# MEMS_audio_board.net
KiCad netlist of a schematic drawn in EAGLE
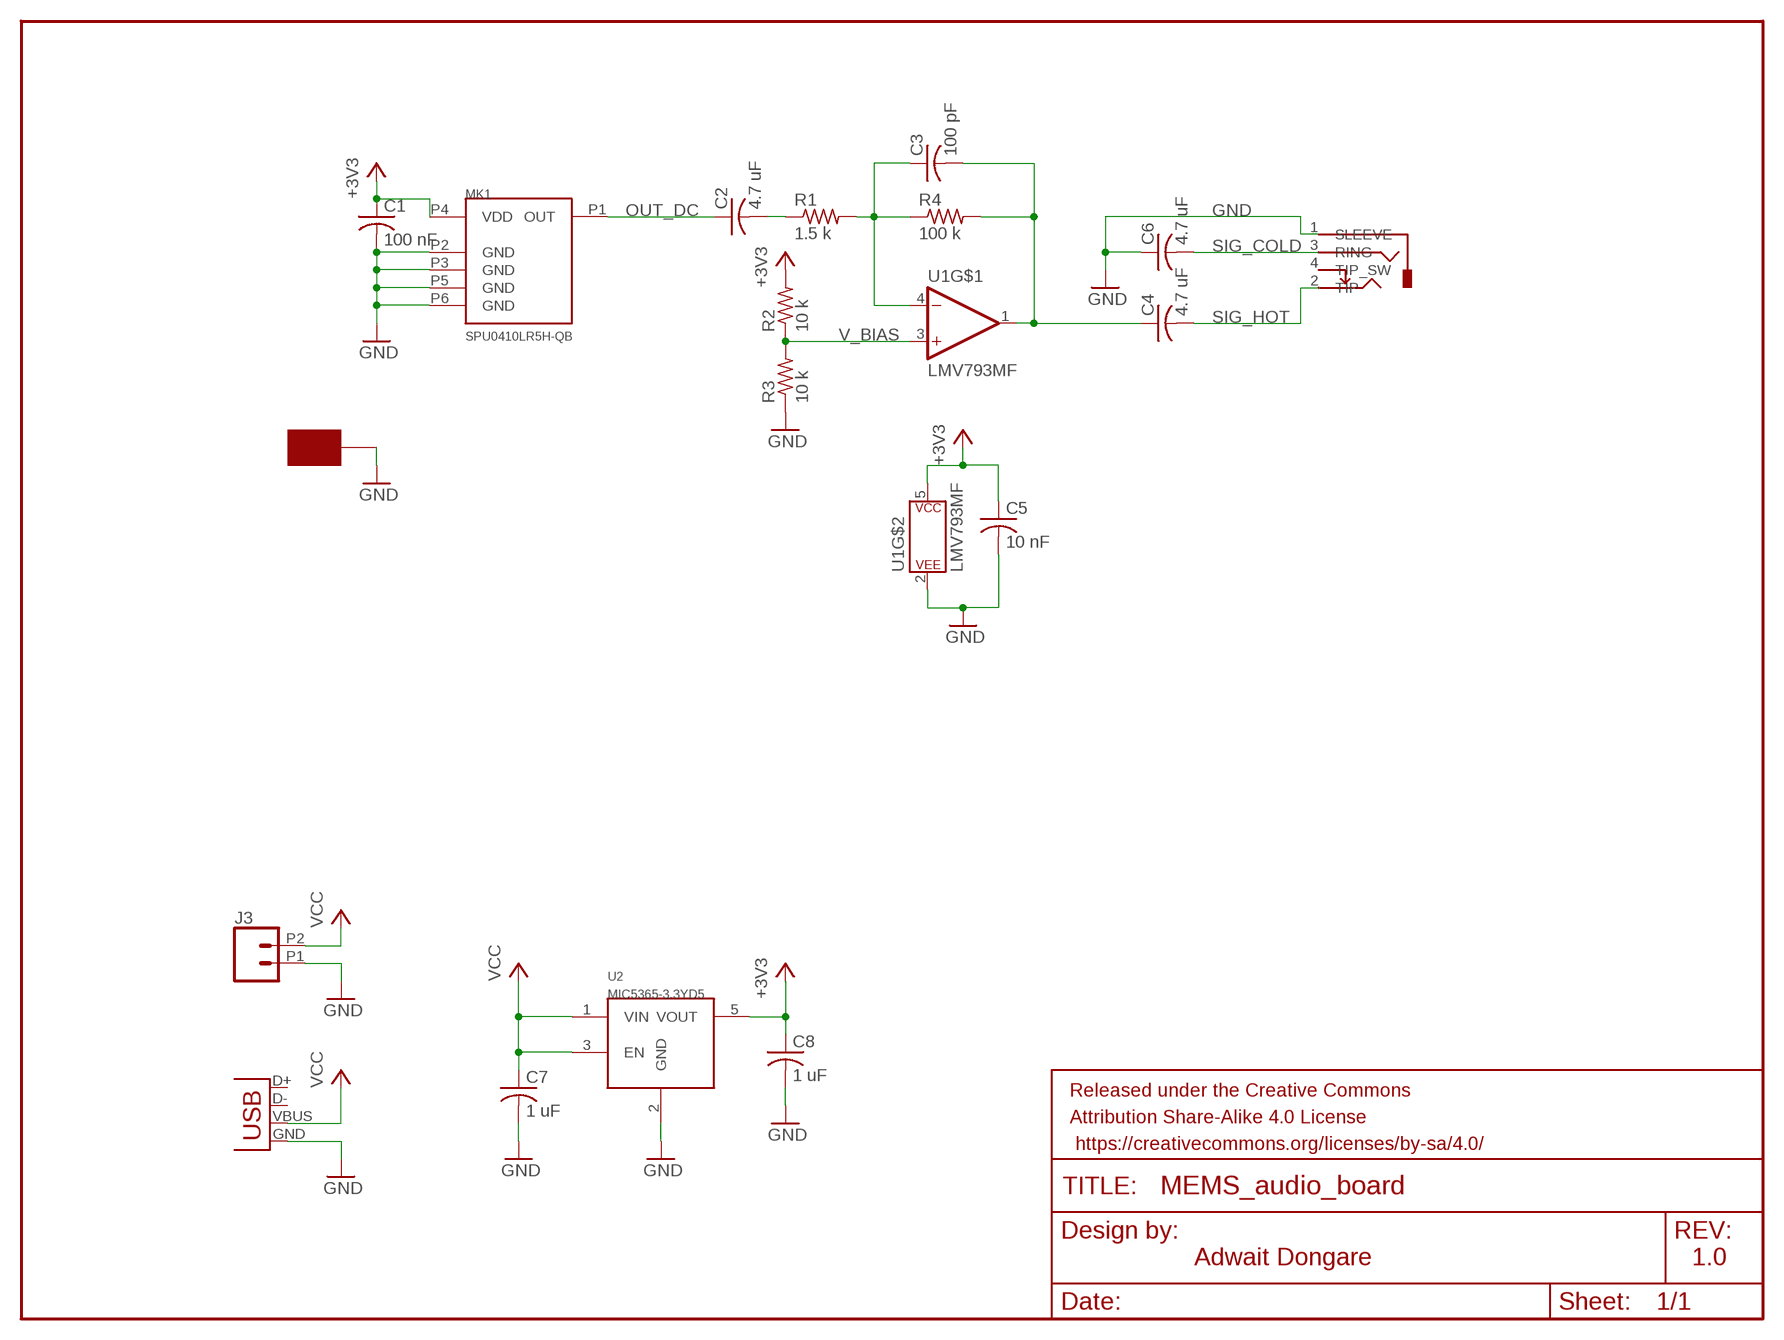
[diagram p0: schematic, sheet 1]

(export (version "E")
  (design (tool "Eeschema 10.0.6"))
  (components
    (comp (ref "C1")
      (value "100 nF")
      (footprint "eagle-import:C0603")
      (libsource (lib "eagle-import") (part "C-USC0603"))
    )
    (comp (ref "C2")
      (value "4.7 uF")
      (footprint "eagle-import:C0603")
      (libsource (lib "eagle-import") (part "C-USC0603"))
    )
    (comp (ref "C3")
      (value "100 pF")
      (footprint "eagle-import:C0603")
      (libsource (lib "eagle-import") (part "C-USC0603"))
    )
    (comp (ref "C4")
      (value "4.7 uF")
      (footprint "eagle-import:C0603")
      (libsource (lib "eagle-import") (part "C-USC0603"))
    )
    (comp (ref "C5")
      (value "10 nF")
      (footprint "eagle-import:C0603")
      (libsource (lib "eagle-import") (part "C-USC0603"))
    )
    (comp (ref "C6")
      (value "4.7 uF")
      (footprint "eagle-import:C0603")
      (libsource (lib "eagle-import") (part "C-USC0603"))
    )
    (comp (ref "C7")
      (value "1 uF")
      (footprint "eagle-import:C0603")
      (libsource (lib "eagle-import") (part "C-USC0603"))
    )
    (comp (ref "C8")
      (value "1 uF")
      (footprint "eagle-import:C0603")
      (libsource (lib "eagle-import") (part "C-USC0603"))
    )
    (comp (ref "FRAME1")
      (value "FRAME-LETTERNO_PACKAGE")
      (footprint "eagle-import:DUMMY")
      (fields (field (name "DESIGNER") "Nobody"))
      (libsource (lib "eagle-import") (part "FRAME-LETTERNO_PACKAGE"))
    )
    (comp (ref "J1")
      (value "SJ-2524-SMT")
      (footprint "eagle-import:SJ-2524-SMT")
      (libsource (lib "eagle-import") (part "SJ-2524-SMT"))
    )
    (comp (ref "J2")
      (value "USBSMD")
      (footprint "eagle-import:USB-MINIB")
      (libsource (lib "eagle-import") (part "USBSMD"))
    )
    (comp (ref "J3")
      (value "CONN_022.54MM_SCREWTERM")
      (footprint "eagle-import:1X02_2.54_SCREWTERM")
      (libsource (lib "eagle-import") (part "CONN_022.54MM_SCREWTERM"))
    )
    (comp (ref "MK1")
      (value "SPU0410LR5H-QB")
      (footprint "eagle-import:SPU0410LR5H-QB")
      (libsource (lib "eagle-import") (part "SPU0410LR5H-QB"))
    )
    (comp (ref "R1")
      (value "1.5 k")
      (footprint "eagle-import:R0603")
      (libsource (lib "eagle-import") (part "R-US_R0603"))
    )
    (comp (ref "R2")
      (value "10 k")
      (footprint "eagle-import:R0603")
      (libsource (lib "eagle-import") (part "R-US_R0603"))
    )
    (comp (ref "R3")
      (value "10 k")
      (footprint "eagle-import:R0603")
      (libsource (lib "eagle-import") (part "R-US_R0603"))
    )
    (comp (ref "R4")
      (value "100 k")
      (footprint "eagle-import:R0603")
      (libsource (lib "eagle-import") (part "R-US_R0603"))
    )
    (comp (ref "TP")
      (value "TEST_PAD-0.4X0.1")
      (footprint "eagle-import:TESTPAD_10.16X2.54")
      (libsource (lib "eagle-import") (part "TEST_PAD-0.4X0.1"))
    )
    (comp (ref "U1")
      (value "LMV793MF")
      (footprint "eagle-import:SOT23-5")
      (libsource (lib "eagle-import") (part "LMV793MF"))
    )
    (comp (ref "U2")
      (value "MIC5365-3.3YD5")
      (footprint "eagle-import:SOT23-5")
      (libsource (lib "eagle-import") (part "MIC5365-X.XXYD5"))
    )
  )
  (nets
    (net (code "1") (name "+3V3") (class "Default")
      (node (ref "C1") (pin "1") (pinfunction "1_1") (pintype "passive"))
      (node (ref "C5") (pin "1") (pinfunction "1_1") (pintype "passive"))
      (node (ref "C8") (pin "1") (pinfunction "1_1") (pintype "passive"))
      (node (ref "MK1") (pin "P4") (pinfunction "VDD_P4") (pintype "power_in"))
      (node (ref "R2") (pin "2") (pinfunction "2_2") (pintype "passive"))
      (node (ref "U1") (pin "5") (pinfunction "P$V+_5") (pintype "bidirectional"))
      (node (ref "U2") (pin "5") (pinfunction "VOUT_5") (pintype "power_in"))
    )
    (net (code "2") (name "/OUT_DC") (class "Default")
      (node (ref "C2") (pin "1") (pinfunction "1_1") (pintype "passive"))
      (node (ref "MK1") (pin "P1") (pinfunction "OUT_P1") (pintype "output"))
    )
    (net (code "3") (name "/SIG_COLD") (class "Default")
      (node (ref "C6") (pin "2") (pinfunction "2_2") (pintype "passive"))
      (node (ref "J1") (pin "3") (pinfunction "RING_3") (pintype "bidirectional"))
    )
    (net (code "4") (name "/SIG_HOT") (class "Default")
      (node (ref "C4") (pin "2") (pinfunction "2_2") (pintype "passive"))
      (node (ref "J1") (pin "2") (pinfunction "TIP_2") (pintype "bidirectional"))
    )
    (net (code "5") (name "/V_BIAS") (class "Default")
      (node (ref "R2") (pin "1") (pinfunction "1_1") (pintype "passive"))
      (node (ref "R3") (pin "2") (pinfunction "2_2") (pintype "passive"))
      (node (ref "U1") (pin "3") (pinfunction "+IN_3") (pintype "input"))
    )
    (net (code "6") (name "GND") (class "Default")
      (node (ref "C1") (pin "2") (pinfunction "2_2") (pintype "passive"))
      (node (ref "C5") (pin "2") (pinfunction "2_2") (pintype "passive"))
      (node (ref "C6") (pin "1") (pinfunction "1_1") (pintype "passive"))
      (node (ref "C7") (pin "2") (pinfunction "2_2") (pintype "passive"))
      (node (ref "C8") (pin "2") (pinfunction "2_2") (pintype "passive"))
      (node (ref "J1") (pin "1") (pinfunction "SLEEVE_1") (pintype "bidirectional"))
      (node (ref "J2") (pin "GND") (pinfunction "GND_GND") (pintype "bidirectional"))
      (node (ref "J3") (pin "P1") (pinfunction "1_P1") (pintype "passive"))
      (node (ref "MK1") (pin "P2") (pinfunction "GND_P2") (pintype "power_in"))
      (node (ref "MK1") (pin "P3") (pinfunction "GND_P3") (pintype "power_in"))
      (node (ref "MK1") (pin "P5") (pinfunction "GND_P5") (pintype "power_in"))
      (node (ref "MK1") (pin "P6") (pinfunction "GND_P6") (pintype "power_in"))
      (node (ref "R3") (pin "1") (pinfunction "1_1") (pintype "passive"))
      (node (ref "TP") (pin "P$1") (pinfunction "P$1_P$1") (pintype "bidirectional"))
      (node (ref "U1") (pin "2") (pinfunction "P$V-_2") (pintype "bidirectional"))
      (node (ref "U2") (pin "2") (pinfunction "GND_2") (pintype "bidirectional"))
    )
    (net (code "7") (name "Net-(C2-Pad2)") (class "Default")
      (node (ref "C2") (pin "2") (pinfunction "2_2") (pintype "passive"))
      (node (ref "R1") (pin "1") (pinfunction "1_1") (pintype "passive"))
    )
    (net (code "8") (name "Net-(U1A--IN)") (class "Default")
      (node (ref "C3") (pin "1") (pinfunction "1_1") (pintype "passive"))
      (node (ref "R1") (pin "2") (pinfunction "2_2") (pintype "passive"))
      (node (ref "R4") (pin "1") (pinfunction "1_1") (pintype "passive"))
      (node (ref "U1") (pin "4") (pinfunction "-IN_4") (pintype "input"))
    )
    (net (code "9") (name "Net-(U1A-OUT)") (class "Default")
      (node (ref "C3") (pin "2") (pinfunction "2_2") (pintype "passive"))
      (node (ref "C4") (pin "1") (pinfunction "1_1") (pintype "passive"))
      (node (ref "R4") (pin "2") (pinfunction "2_2") (pintype "passive"))
      (node (ref "U1") (pin "1") (pinfunction "OUT_1") (pintype "output"))
    )
    (net (code "10") (name "VCC") (class "Default")
      (node (ref "C7") (pin "1") (pinfunction "1_1") (pintype "passive"))
      (node (ref "J2") (pin "VBUS") (pinfunction "VBUS_VBUS") (pintype "bidirectional"))
      (node (ref "J3") (pin "P2") (pinfunction "2_P2") (pintype "passive"))
      (node (ref "U2") (pin "1") (pinfunction "VIN_1") (pintype "power_in"))
      (node (ref "U2") (pin "3") (pinfunction "EN_3") (pintype "input"))
    )
    (net (code "11") (name "unconnected-(J1-TIP_SW-Pad4)") (class "Default")
      (node (ref "J1") (pin "4") (pinfunction "TIP_SW_4") (pintype "bidirectional"))
    )
    (net (code "12") (name "unconnected-(J2-PadD+)") (class "Default")
      (node (ref "J2") (pin "D+") (pinfunction "D+_D+") (pintype "bidirectional"))
    )
    (net (code "13") (name "unconnected-(J2-PadD-)") (class "Default")
      (node (ref "J2") (pin "D-") (pinfunction "D-_D-") (pintype "bidirectional"))
    )
  )
)
